# Interface2.net
KiCad netlist of a schematic drawn in Altium Designer
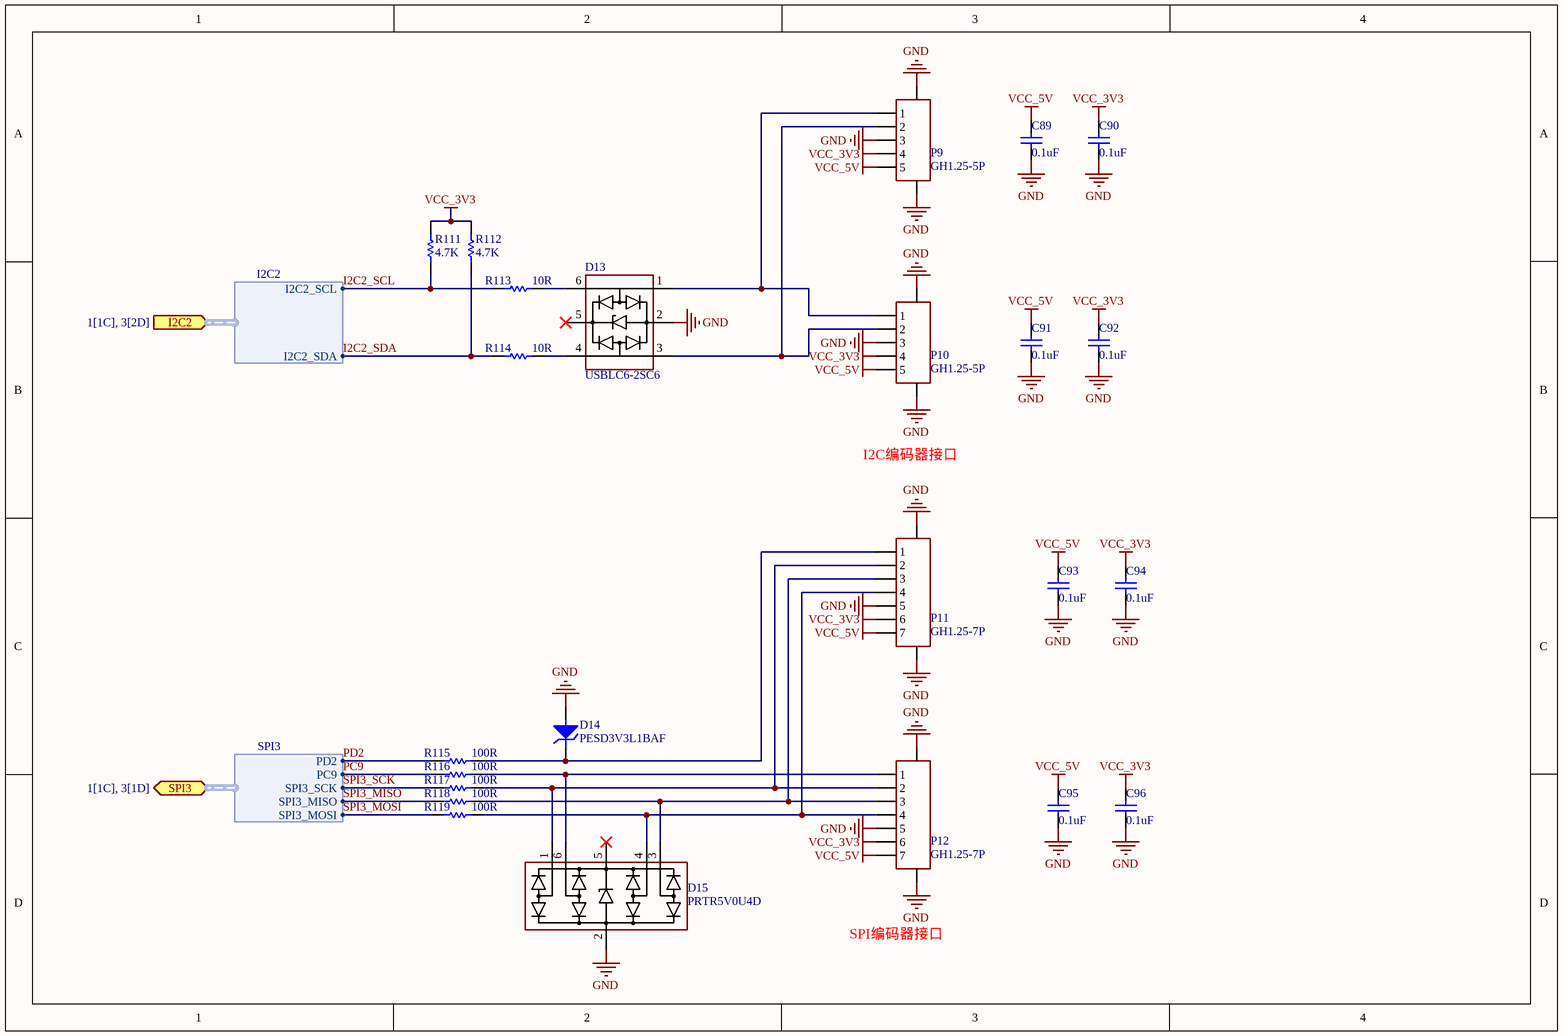
[diagram p0: Interface2.SchDoc]

(export (version "E")
  (design (tool "Eeschema 10.0.6"))
  (components
    (comp (ref "C89")
      (value "0.1uF")
      (footprint "C0603_NS")
      (description "Capacitor")
      (libsource (lib "Miscellaneous Devices") (part "Cap"))
    )
    (comp (ref "C90")
      (value "0.1uF")
      (footprint "C0603_NS")
      (description "Capacitor")
      (libsource (lib "Miscellaneous Devices") (part "Cap"))
    )
    (comp (ref "C91")
      (value "0.1uF")
      (footprint "C0603_NS")
      (description "Capacitor")
      (libsource (lib "Miscellaneous Devices") (part "Cap"))
    )
    (comp (ref "C92")
      (value "0.1uF")
      (footprint "C0603_NS")
      (description "Capacitor")
      (libsource (lib "Miscellaneous Devices") (part "Cap"))
    )
    (comp (ref "C93")
      (value "0.1uF")
      (footprint "C0603_NS")
      (description "Capacitor")
      (libsource (lib "Miscellaneous Devices") (part "Cap"))
    )
    (comp (ref "C94")
      (value "0.1uF")
      (footprint "C0603_NS")
      (description "Capacitor")
      (libsource (lib "Miscellaneous Devices") (part "Cap"))
    )
    (comp (ref "C95")
      (value "0.1uF")
      (footprint "C0603_NS")
      (description "Capacitor")
      (libsource (lib "Miscellaneous Devices") (part "Cap"))
    )
    (comp (ref "C96")
      (value "0.1uF")
      (footprint "C0603_NS")
      (description "Capacitor")
      (libsource (lib "Miscellaneous Devices") (part "Cap"))
    )
    (comp (ref "D13")
      (value "USBLC6-2SC6")
      (footprint "SOT23-6N")
      (libsource (lib "my_library") (part "USBLC6-2SC6"))
    )
    (comp (ref "D14")
      (value "PESD3V3L1BAF")
      (footprint "SOD-323")
      (description "单向瞬态抑制二极管")
      (libsource (lib "my_library") (part "TVS2"))
    )
    (comp (ref "D15")
      (value "PRTR5V0U4D")
      (footprint "SOT-457(SC-74)")
      (libsource (lib "my_library") (part "PRTR5V0U4D"))
    )
    (comp (ref "P9")
      (value "GH1.25-5P")
      (footprint "A1257WR-S-5P")
      (libsource (lib "my_library") (part "Header5"))
    )
    (comp (ref "P10")
      (value "GH1.25-5P")
      (footprint "A1257WR-S-5P")
      (libsource (lib "my_library") (part "Header5"))
    )
    (comp (ref "P11")
      (value "GH1.25-7P")
      (footprint "A1257WR-S-7P")
      (libsource (lib "my_library") (part "Header7"))
    )
    (comp (ref "P12")
      (value "GH1.25-7P")
      (footprint "A1257WR-S-7P")
      (libsource (lib "my_library") (part "Header7"))
    )
    (comp (ref "R111")
      (value "4.7K")
      (footprint "R0603_NS")
      (description "Resistor")
      (libsource (lib "Miscellaneous Devices") (part "Res1"))
    )
    (comp (ref "R112")
      (value "4.7K")
      (footprint "R0603_NS")
      (description "Resistor")
      (libsource (lib "Miscellaneous Devices") (part "Res1"))
    )
    (comp (ref "R113")
      (value "10R")
      (footprint "R0603_NS")
      (description "Resistor")
      (libsource (lib "Miscellaneous Devices") (part "Res1"))
    )
    (comp (ref "R114")
      (value "10R")
      (footprint "R0603_NS")
      (description "Resistor")
      (libsource (lib "Miscellaneous Devices") (part "Res1"))
    )
    (comp (ref "R115")
      (value "100R")
      (footprint "R0603_NS")
      (description "Resistor")
      (libsource (lib "Miscellaneous Devices") (part "Res1"))
    )
    (comp (ref "R116")
      (value "100R")
      (footprint "R0603_NS")
      (description "Resistor")
      (libsource (lib "Miscellaneous Devices") (part "Res1"))
    )
    (comp (ref "R117")
      (value "100R")
      (footprint "R0603_NS")
      (description "Resistor")
      (libsource (lib "Miscellaneous Devices") (part "Res1"))
    )
    (comp (ref "R118")
      (value "100R")
      (footprint "R0603_NS")
      (description "Resistor")
      (libsource (lib "Miscellaneous Devices") (part "Res1"))
    )
    (comp (ref "R119")
      (value "100R")
      (footprint "R0603_NS")
      (description "Resistor")
      (libsource (lib "Miscellaneous Devices") (part "Res1"))
    )
  )
  (nets
    (net (code "3") (name "/I2C2_SCL") (class "Default")
      (node (ref "R111") (pin "1") (pinfunction "1_1") (pintype "passive"))
      (node (ref "R113") (pin "1") (pinfunction "1_1") (pintype "passive"))
    )
    (net (code "4") (name "/I2C2_SDA") (class "Default")
      (node (ref "R112") (pin "1") (pinfunction "1_1") (pintype "passive"))
      (node (ref "R114") (pin "1") (pinfunction "1_1") (pintype "passive"))
    )
    (net (code "5") (name "/PC9") (class "Default")
      (node (ref "R116") (pin "1") (pinfunction "1_1") (pintype "passive"))
    )
    (net (code "6") (name "/PD2") (class "Default")
      (node (ref "R115") (pin "1") (pinfunction "1_1") (pintype "passive"))
    )
    (net (code "7") (name "/SPI3_MISO") (class "Default")
      (node (ref "R118") (pin "1") (pinfunction "1_1") (pintype "passive"))
    )
    (net (code "8") (name "/SPI3_MOSI") (class "Default")
      (node (ref "R119") (pin "1") (pinfunction "1_1") (pintype "passive"))
    )
    (net (code "9") (name "/SPI3_SCK") (class "Default")
      (node (ref "R117") (pin "1") (pinfunction "1_1") (pintype "passive"))
    )
    (net (code "12") (name "GND") (class "Default")
      (node (ref "C89") (pin "1") (pinfunction "1_1") (pintype "passive"))
      (node (ref "C90") (pin "1") (pinfunction "1_1") (pintype "passive"))
      (node (ref "C91") (pin "1") (pinfunction "1_1") (pintype "passive"))
      (node (ref "C92") (pin "1") (pinfunction "1_1") (pintype "passive"))
      (node (ref "C93") (pin "1") (pinfunction "1_1") (pintype "passive"))
      (node (ref "C94") (pin "1") (pinfunction "1_1") (pintype "passive"))
      (node (ref "C95") (pin "1") (pinfunction "1_1") (pintype "passive"))
      (node (ref "C96") (pin "1") (pinfunction "1_1") (pintype "passive"))
      (node (ref "D13") (pin "2") (pinfunction "2_2") (pintype "passive"))
      (node (ref "D14") (pin "A") (pinfunction "A_A") (pintype "passive"))
      (node (ref "D15") (pin "2") (pinfunction "2_2") (pintype "passive"))
      (node (ref "P10") (pin "0") (pinfunction "0_0") (pintype "passive"))
      (node (ref "P10") (pin "3") (pinfunction "3_3") (pintype "passive"))
      (node (ref "P11") (pin "0") (pinfunction "0_0") (pintype "passive"))
      (node (ref "P11") (pin "5") (pinfunction "5_5") (pintype "passive"))
      (node (ref "P12") (pin "0") (pinfunction "0_0") (pintype "passive"))
      (node (ref "P12") (pin "5") (pinfunction "5_5") (pintype "passive"))
      (node (ref "P9") (pin "0") (pinfunction "0_0") (pintype "passive"))
      (node (ref "P9") (pin "3") (pinfunction "3_3") (pintype "passive"))
    )
    (net (code "13") (name "Net-(D13-Pad1)") (class "Default")
      (node (ref "D13") (pin "1") (pinfunction "1_1") (pintype "passive"))
      (node (ref "P10") (pin "1") (pinfunction "1_1") (pintype "passive"))
      (node (ref "P9") (pin "1") (pinfunction "1_1") (pintype "passive"))
    )
    (net (code "14") (name "Net-(D13-Pad3)") (class "Default")
      (node (ref "D13") (pin "3") (pinfunction "3_3") (pintype "passive"))
      (node (ref "P10") (pin "2") (pinfunction "2_2") (pintype "passive"))
      (node (ref "P9") (pin "2") (pinfunction "2_2") (pintype "passive"))
    )
    (net (code "15") (name "Net-(D13-Pad4)") (class "Default")
      (node (ref "D13") (pin "4") (pinfunction "4_4") (pintype "passive"))
      (node (ref "R114") (pin "2") (pinfunction "2_2") (pintype "passive"))
    )
    (net (code "16") (name "Net-(D13-Pad6)") (class "Default")
      (node (ref "D13") (pin "6") (pinfunction "6_6") (pintype "passive"))
      (node (ref "R113") (pin "2") (pinfunction "2_2") (pintype "passive"))
    )
    (net (code "17") (name "Net-(D14-PadK)") (class "Default")
      (node (ref "D14") (pin "K") (pinfunction "K_K") (pintype "passive"))
      (node (ref "P11") (pin "1") (pinfunction "1_1") (pintype "passive"))
      (node (ref "R115") (pin "2") (pinfunction "2_2") (pintype "passive"))
    )
    (net (code "18") (name "Net-(D15-Pad1)") (class "Default")
      (node (ref "D15") (pin "1") (pinfunction "1_1") (pintype "passive"))
      (node (ref "P11") (pin "2") (pinfunction "2_2") (pintype "passive"))
      (node (ref "P12") (pin "2") (pinfunction "2_2") (pintype "passive"))
      (node (ref "R117") (pin "2") (pinfunction "2_2") (pintype "passive"))
    )
    (net (code "19") (name "Net-(D15-Pad3)") (class "Default")
      (node (ref "D15") (pin "3") (pinfunction "3_3") (pintype "passive"))
      (node (ref "P11") (pin "3") (pinfunction "3_3") (pintype "passive"))
      (node (ref "P12") (pin "3") (pinfunction "3_3") (pintype "passive"))
      (node (ref "R118") (pin "2") (pinfunction "2_2") (pintype "passive"))
    )
    (net (code "20") (name "Net-(D15-Pad4)") (class "Default")
      (node (ref "D15") (pin "4") (pinfunction "4_4") (pintype "passive"))
      (node (ref "P11") (pin "4") (pinfunction "4_4") (pintype "passive"))
      (node (ref "P12") (pin "4") (pinfunction "4_4") (pintype "passive"))
      (node (ref "R119") (pin "2") (pinfunction "2_2") (pintype "passive"))
    )
    (net (code "21") (name "Net-(D15-Pad6)") (class "Default")
      (node (ref "D15") (pin "6") (pinfunction "6_6") (pintype "passive"))
      (node (ref "P12") (pin "1") (pinfunction "1_1") (pintype "passive"))
      (node (ref "R116") (pin "2") (pinfunction "2_2") (pintype "passive"))
    )
    (net (code "22") (name "VCC_3V3") (class "Default")
      (node (ref "C90") (pin "2") (pinfunction "2_2") (pintype "passive"))
      (node (ref "C92") (pin "2") (pinfunction "2_2") (pintype "passive"))
      (node (ref "C94") (pin "2") (pinfunction "2_2") (pintype "passive"))
      (node (ref "C96") (pin "2") (pinfunction "2_2") (pintype "passive"))
      (node (ref "P10") (pin "4") (pinfunction "4_4") (pintype "passive"))
      (node (ref "P11") (pin "6") (pinfunction "6_6") (pintype "passive"))
      (node (ref "P12") (pin "6") (pinfunction "6_6") (pintype "passive"))
      (node (ref "P9") (pin "4") (pinfunction "4_4") (pintype "passive"))
      (node (ref "R111") (pin "2") (pinfunction "2_2") (pintype "passive"))
      (node (ref "R112") (pin "2") (pinfunction "2_2") (pintype "passive"))
    )
    (net (code "23") (name "VCC_5V") (class "Default")
      (node (ref "C89") (pin "2") (pinfunction "2_2") (pintype "passive"))
      (node (ref "C91") (pin "2") (pinfunction "2_2") (pintype "passive"))
      (node (ref "C93") (pin "2") (pinfunction "2_2") (pintype "passive"))
      (node (ref "C95") (pin "2") (pinfunction "2_2") (pintype "passive"))
      (node (ref "P10") (pin "5") (pinfunction "5_5") (pintype "passive"))
      (node (ref "P11") (pin "7") (pinfunction "7_7") (pintype "passive"))
      (node (ref "P12") (pin "7") (pinfunction "7_7") (pintype "passive"))
      (node (ref "P9") (pin "5") (pinfunction "5_5") (pintype "passive"))
    )
    (net (code "24") (name "unconnected-(D13-Pad5)") (class "Default")
      (node (ref "D13") (pin "5") (pinfunction "5_5") (pintype "passive+no_connect"))
    )
    (net (code "25") (name "unconnected-(D15-Pad5)") (class "Default")
      (node (ref "D15") (pin "5") (pinfunction "5_5") (pintype "passive+no_connect"))
    )
  )
)
